# Universal_Transceiver.net
KiCad netlist of a schematic drawn in EasyEDA Pro
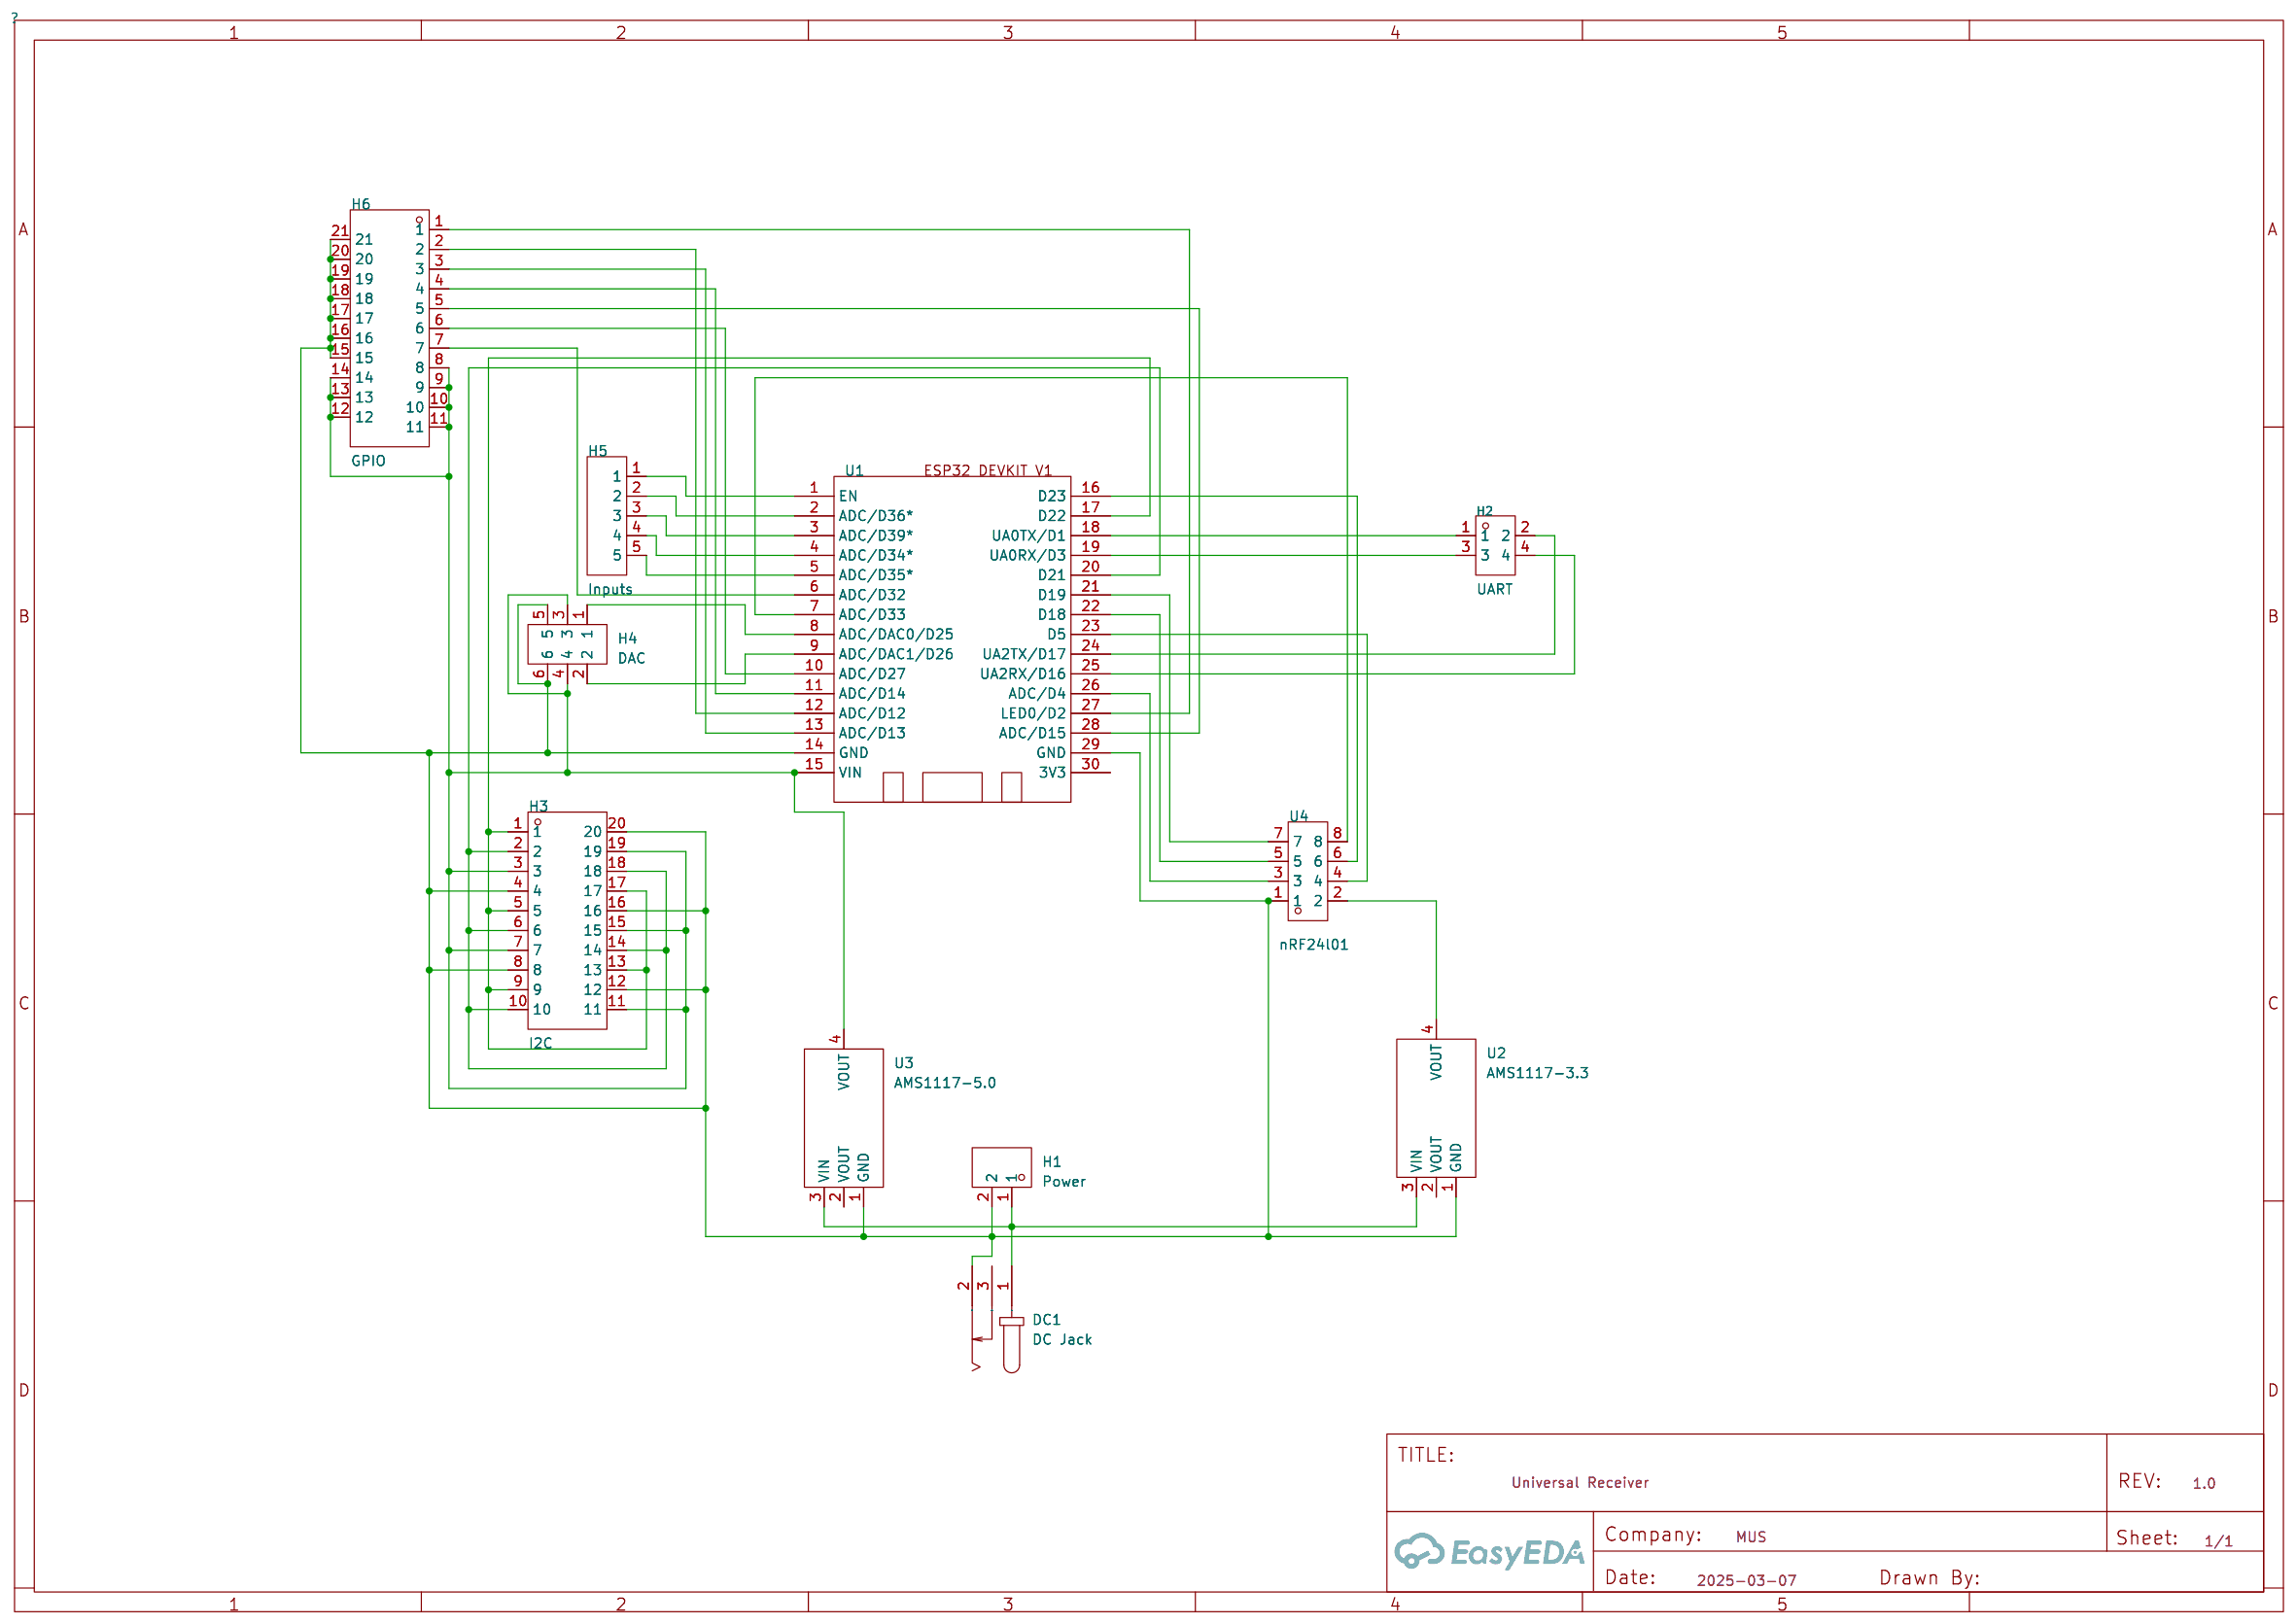
[diagram p0: schematic sheet]

(export (version "E")
  (design (tool "Eeschema 10.0.6"))
  (components
    (comp (ref "DC1")
      (value "DC Jack")
      (footprint "easyedapro:DC-IN-TH_DC-005-5A-2.0")
      (fields (field (name "Manufacturer") "XKB Connection(中国星坤)"))
      (libsource (lib "easyedapro") (part "DC-005-5A-2.0"))
    )
    (comp (ref "H1")
      (value "Power")
      (footprint "easyedapro:HDR-TH_2P-P2.54-V-M_5")
      (fields (field (name "Manufacturer") "HCTL(华灿天禄)"))
      (libsource (lib "easyedapro") (part "PZ254-1-02-Z-C"))
    )
    (comp (ref "H2")
      (value "UART")
      (footprint "easyedapro:HDR-TH_4P-P2.54-V-M-R2-C2-S2.54")
      (fields (field (name "Manufacturer") "HCTL(华灿天禄)"))
      (libsource (lib "easyedapro") (part "PZ254-2-02-Z-2.5-G1"))
    )
    (comp (ref "H3")
      (value "I2C")
      (footprint "easyedapro:HDR-TH_20P-P2.54-V-M-R4-C5-S2.54")
      (fields (field (name "Manufacturer") "hanxia(韩下)"))
      (libsource (lib "easyedapro") (part "HX PZ2.54-4X5P ZZ"))
    )
    (comp (ref "H4")
      (value "DAC")
      (footprint "easyedapro:HDR-TH_6P-P2.54-V-M-R2-C3-S2.54")
      (description "Pin Structure:2x3P Pitch:2.54mm Mounting Type:Straight Number of Rows:Double Row Number of Pins:6P")
      (fields (field (name "Manufacturer") "CONNFLY"))
      (libsource (lib "easyedapro") (part "DS1021-2X3SF11-B"))
    )
    (comp (ref "H5")
      (value "Inputs")
      (footprint "easyedapro:HDR-TH_5P-P2.54-V-M")
      (fields (field (name "Manufacturer") "XFCN(兴飞)"))
      (libsource (lib "easyedapro") (part "PZ254V-11-05P"))
    )
    (comp (ref "H6")
      (value "GPIO")
      (footprint "easyedapro:CONN-TH_HX-PZ2.54-3X7P-ZZ")
      (fields (field (name "Manufacturer") "hanxia(韩下)"))
      (libsource (lib "easyedapro") (part "HX PZ2.54-3X7P ZZ"))
    )
    (comp (ref "U1")
      (value "~")
      (footprint "easyedapro:ESP32 Devkit V1")
      (libsource (lib "easyedapro") (part "ESP32 Devkit V1"))
    )
    (comp (ref "U2")
      (value "AMS1117-3.3")
      (footprint "easyedapro:SOT-223-3_L6.5-W3.4-P2.30-LS7.0-BR")
      (fields (field (name "Manufacturer") "AMS"))
      (libsource (lib "easyedapro") (part "AMS1117-3.3"))
    )
    (comp (ref "U3")
      (value "AMS1117-5.0")
      (footprint "easyedapro:SOT-223_L6.5-W3.5-P2.30-LS7.0-BR")
      (fields (field (name "Manufacturer") "AMS"))
      (libsource (lib "easyedapro") (part "AMS1117-5.0"))
    )
    (comp (ref "U4")
      (value "nRF24l01")
      (footprint "easyedapro:HDR-TH_8P-P2.54-V-F-R2-C4-S2.54")
      (fields (field (name "Manufacturer") "ZHOURI(洲日)"))
      (libsource (lib "easyedapro") (part "2.54-2*4"))
    )
  )
  (nets
    (net (code "1") (name "Net-(U1-ADC{slash}D4)") (class "Default")
      (node (ref "U1") (pin "26") (pinfunction "ADC/D4_26") (pintype "bidirectional"))
      (node (ref "U4") (pin "3") (pinfunction "3_3") (pintype "unspecified"))
    )
    (net (code "2") (name "Net-(U1-ADC{slash}D12)") (class "Default")
      (node (ref "H6") (pin "2") (pinfunction "2_2") (pintype "unspecified"))
      (node (ref "U1") (pin "12") (pinfunction "ADC/D12_12") (pintype "bidirectional"))
    )
    (net (code "3") (name "Net-(U1-ADC{slash}D13)") (class "Default")
      (node (ref "H6") (pin "3") (pinfunction "3_3") (pintype "unspecified"))
      (node (ref "U1") (pin "13") (pinfunction "ADC/D13_13") (pintype "bidirectional"))
    )
    (net (code "4") (name "Net-(U1-ADC{slash}D14)") (class "Default")
      (node (ref "H6") (pin "4") (pinfunction "4_4") (pintype "unspecified"))
      (node (ref "U1") (pin "11") (pinfunction "ADC/D14_11") (pintype "bidirectional"))
    )
    (net (code "5") (name "Net-(U1-ADC{slash}D15)") (class "Default")
      (node (ref "H6") (pin "5") (pinfunction "5_5") (pintype "unspecified"))
      (node (ref "U1") (pin "28") (pinfunction "ADC/D15_28") (pintype "bidirectional"))
    )
    (net (code "6") (name "Net-(U1-ADC{slash}D27)") (class "Default")
      (node (ref "H6") (pin "6") (pinfunction "6_6") (pintype "unspecified"))
      (node (ref "U1") (pin "10") (pinfunction "ADC/D27_10") (pintype "bidirectional"))
    )
    (net (code "7") (name "Net-(U1-ADC{slash}D32)") (class "Default")
      (node (ref "H6") (pin "7") (pinfunction "7_7") (pintype "unspecified"))
      (node (ref "U1") (pin "6") (pinfunction "ADC/D32_6") (pintype "bidirectional"))
    )
    (net (code "8") (name "Net-(U1-ADC{slash}D33)") (class "Default")
      (node (ref "U1") (pin "7") (pinfunction "ADC/D33_7") (pintype "bidirectional"))
      (node (ref "U4") (pin "8") (pinfunction "8_8") (pintype "unspecified"))
    )
    (net (code "9") (name "Net-(U1-ADC{slash}D34*)") (class "Default")
      (node (ref "H5") (pin "4") (pinfunction "4_4") (pintype "unspecified"))
      (node (ref "U1") (pin "4") (pinfunction "ADC/D34*_4") (pintype "input"))
    )
    (net (code "10") (name "Net-(U1-ADC{slash}D35*)") (class "Default")
      (node (ref "H5") (pin "5") (pinfunction "5_5") (pintype "unspecified"))
      (node (ref "U1") (pin "5") (pinfunction "ADC/D35*_5") (pintype "input"))
    )
    (net (code "11") (name "Net-(U1-ADC{slash}D36*)") (class "Default")
      (node (ref "H5") (pin "2") (pinfunction "2_2") (pintype "unspecified"))
      (node (ref "U1") (pin "2") (pinfunction "ADC/D36*_2") (pintype "input"))
    )
    (net (code "12") (name "Net-(U1-ADC{slash}D39*)") (class "Default")
      (node (ref "H5") (pin "3") (pinfunction "3_3") (pintype "unspecified"))
      (node (ref "U1") (pin "3") (pinfunction "ADC/D39*_3") (pintype "input"))
    )
    (net (code "13") (name "Net-(U1-ADC{slash}DAC0{slash}D25)") (class "Default")
      (node (ref "H4") (pin "1") (pinfunction "1_1") (pintype "unspecified"))
      (node (ref "U1") (pin "8") (pinfunction "ADC/DAC0/D25_8") (pintype "bidirectional"))
    )
    (net (code "14") (name "Net-(U1-ADC{slash}DAC1{slash}D26)") (class "Default")
      (node (ref "H4") (pin "2") (pinfunction "2_2") (pintype "unspecified"))
      (node (ref "U1") (pin "9") (pinfunction "ADC/DAC1/D26_9") (pintype "bidirectional"))
    )
    (net (code "15") (name "Net-(U1-D5)") (class "Default")
      (node (ref "U1") (pin "23") (pinfunction "D5_23") (pintype "bidirectional"))
      (node (ref "U4") (pin "4") (pinfunction "4_4") (pintype "unspecified"))
    )
    (net (code "16") (name "Net-(U1-D18)") (class "Default")
      (node (ref "U1") (pin "22") (pinfunction "D18_22") (pintype "bidirectional"))
      (node (ref "U4") (pin "5") (pinfunction "5_5") (pintype "unspecified"))
    )
    (net (code "17") (name "Net-(U1-D19)") (class "Default")
      (node (ref "U1") (pin "21") (pinfunction "D19_21") (pintype "bidirectional"))
      (node (ref "U4") (pin "7") (pinfunction "7_7") (pintype "unspecified"))
    )
    (net (code "18") (name "Net-(U1-D21)") (class "Default")
      (node (ref "H3") (pin "10") (pinfunction "10_10") (pintype "unspecified"))
      (node (ref "H3") (pin "14") (pinfunction "14_14") (pintype "unspecified"))
      (node (ref "H3") (pin "18") (pinfunction "18_18") (pintype "unspecified"))
      (node (ref "H3") (pin "2") (pinfunction "2_2") (pintype "unspecified"))
      (node (ref "H3") (pin "6") (pinfunction "6_6") (pintype "unspecified"))
      (node (ref "U1") (pin "20") (pinfunction "D21_20") (pintype "bidirectional"))
    )
    (net (code "19") (name "Net-(U1-D22)") (class "Default")
      (node (ref "H3") (pin "1") (pinfunction "1_1") (pintype "unspecified"))
      (node (ref "H3") (pin "13") (pinfunction "13_13") (pintype "unspecified"))
      (node (ref "H3") (pin "17") (pinfunction "17_17") (pintype "unspecified"))
      (node (ref "H3") (pin "5") (pinfunction "5_5") (pintype "unspecified"))
      (node (ref "H3") (pin "9") (pinfunction "9_9") (pintype "unspecified"))
      (node (ref "U1") (pin "17") (pinfunction "D22_17") (pintype "bidirectional"))
    )
    (net (code "20") (name "Net-(U1-D23)") (class "Default")
      (node (ref "U1") (pin "16") (pinfunction "D23_16") (pintype "bidirectional"))
      (node (ref "U4") (pin "6") (pinfunction "6_6") (pintype "unspecified"))
    )
    (net (code "21") (name "Net-(U1-EN)") (class "Default")
      (node (ref "H5") (pin "1") (pinfunction "1_1") (pintype "unspecified"))
      (node (ref "U1") (pin "1") (pinfunction "EN_1") (pintype "bidirectional"))
    )
    (net (code "22") (name "Net-(U1-LED0{slash}D2)") (class "Default")
      (node (ref "H6") (pin "1") (pinfunction "1_1") (pintype "unspecified"))
      (node (ref "U1") (pin "27") (pinfunction "LED0/D2_27") (pintype "bidirectional"))
    )
    (net (code "23") (name "Net-(U1-UA0RX{slash}D3)") (class "Default")
      (node (ref "H2") (pin "3") (pinfunction "3_3") (pintype "input"))
      (node (ref "U1") (pin "19") (pinfunction "UA0RX/D3_19") (pintype "bidirectional"))
    )
    (net (code "24") (name "Net-(U1-UA0TX{slash}D1)") (class "Default")
      (node (ref "H2") (pin "1") (pinfunction "1_1") (pintype "input"))
      (node (ref "U1") (pin "18") (pinfunction "UA0TX/D1_18") (pintype "bidirectional"))
    )
    (net (code "25") (name "Net-(U1-UA2RX{slash}D16)") (class "Default")
      (node (ref "H2") (pin "4") (pinfunction "4_4") (pintype "input"))
      (node (ref "U1") (pin "25") (pinfunction "UA2RX/D16_25") (pintype "bidirectional"))
    )
    (net (code "26") (name "Net-(U1-UA2TX{slash}D17)") (class "Default")
      (node (ref "H2") (pin "2") (pinfunction "2_2") (pintype "input"))
      (node (ref "U1") (pin "24") (pinfunction "UA2TX/D17_24") (pintype "bidirectional"))
    )
    (net (code "27") (name "Net-(U1-VIN)") (class "Default")
      (node (ref "H3") (pin "11") (pinfunction "11_11") (pintype "unspecified"))
      (node (ref "H3") (pin "15") (pinfunction "15_15") (pintype "unspecified"))
      (node (ref "H3") (pin "19") (pinfunction "19_19") (pintype "unspecified"))
      (node (ref "H3") (pin "3") (pinfunction "3_3") (pintype "unspecified"))
      (node (ref "H3") (pin "7") (pinfunction "7_7") (pintype "unspecified"))
      (node (ref "H4") (pin "3") (pinfunction "3_3") (pintype "unspecified"))
      (node (ref "H4") (pin "4") (pinfunction "4_4") (pintype "unspecified"))
      (node (ref "H6") (pin "10") (pinfunction "10_10") (pintype "unspecified"))
      (node (ref "H6") (pin "11") (pinfunction "11_11") (pintype "unspecified"))
      (node (ref "H6") (pin "12") (pinfunction "12_12") (pintype "unspecified"))
      (node (ref "H6") (pin "13") (pinfunction "13_13") (pintype "unspecified"))
      (node (ref "H6") (pin "14") (pinfunction "14_14") (pintype "unspecified"))
      (node (ref "H6") (pin "8") (pinfunction "8_8") (pintype "unspecified"))
      (node (ref "H6") (pin "9") (pinfunction "9_9") (pintype "unspecified"))
      (node (ref "U1") (pin "15") (pinfunction "VIN_15") (pintype "input"))
      (node (ref "U3") (pin "4") (pinfunction "VOUT_4") (pintype "unspecified"))
    )
    (net (code "28") (name "Net-(U2-GND)") (class "Default")
      (node (ref "DC1") (pin "2") (pinfunction "2_2") (pintype "unspecified"))
      (node (ref "H1") (pin "2") (pinfunction "2_2") (pintype "unspecified"))
      (node (ref "H3") (pin "12") (pinfunction "12_12") (pintype "unspecified"))
      (node (ref "H3") (pin "16") (pinfunction "16_16") (pintype "unspecified"))
      (node (ref "H3") (pin "20") (pinfunction "20_20") (pintype "unspecified"))
      (node (ref "H3") (pin "4") (pinfunction "4_4") (pintype "unspecified"))
      (node (ref "H3") (pin "8") (pinfunction "8_8") (pintype "unspecified"))
      (node (ref "H4") (pin "5") (pinfunction "5_5") (pintype "unspecified"))
      (node (ref "H4") (pin "6") (pinfunction "6_6") (pintype "unspecified"))
      (node (ref "H6") (pin "15") (pinfunction "15_15") (pintype "unspecified"))
      (node (ref "H6") (pin "16") (pinfunction "16_16") (pintype "unspecified"))
      (node (ref "H6") (pin "17") (pinfunction "17_17") (pintype "unspecified"))
      (node (ref "H6") (pin "18") (pinfunction "18_18") (pintype "unspecified"))
      (node (ref "H6") (pin "19") (pinfunction "19_19") (pintype "unspecified"))
      (node (ref "H6") (pin "20") (pinfunction "20_20") (pintype "unspecified"))
      (node (ref "H6") (pin "21") (pinfunction "21_21") (pintype "unspecified"))
      (node (ref "U1") (pin "14") (pinfunction "GND_14") (pintype "bidirectional"))
      (node (ref "U1") (pin "29") (pinfunction "GND_29") (pintype "bidirectional"))
      (node (ref "U2") (pin "1") (pinfunction "GND_1") (pintype "unspecified"))
      (node (ref "U3") (pin "1") (pinfunction "GND_1") (pintype "unspecified"))
      (node (ref "U4") (pin "1") (pinfunction "1_1") (pintype "unspecified"))
    )
    (net (code "29") (name "Net-(U2-VIN)") (class "Default")
      (node (ref "DC1") (pin "1") (pinfunction "1_1") (pintype "unspecified"))
      (node (ref "H1") (pin "1") (pinfunction "1_1") (pintype "unspecified"))
      (node (ref "U2") (pin "3") (pinfunction "VIN_3") (pintype "unspecified"))
      (node (ref "U3") (pin "3") (pinfunction "VIN_3") (pintype "unspecified"))
    )
    (net (code "30") (name "Net-(U2-VOUT-Pad4)") (class "Default")
      (node (ref "U2") (pin "4") (pinfunction "VOUT_4") (pintype "unspecified"))
      (node (ref "U4") (pin "2") (pinfunction "2_2") (pintype "unspecified"))
    )
    (net (code "31") (name "unconnected-(DC1-Pad3)") (class "Default")
      (node (ref "DC1") (pin "3") (pinfunction "3_3") (pintype "unspecified"))
    )
    (net (code "32") (name "unconnected-(U1-3V3-Pad30)") (class "Default")
      (node (ref "U1") (pin "30") (pinfunction "3V3_30") (pintype "bidirectional"))
    )
    (net (code "33") (name "unconnected-(U2-VOUT-Pad2)") (class "Default")
      (node (ref "U2") (pin "2") (pinfunction "VOUT_2") (pintype "unspecified"))
    )
    (net (code "34") (name "unconnected-(U3-VOUT-Pad2)") (class "Default")
      (node (ref "U3") (pin "2") (pinfunction "VOUT_2") (pintype "unspecified"))
    )
  )
)
